# Switch.net
KiCad netlist of a schematic drawn in Altium Designer
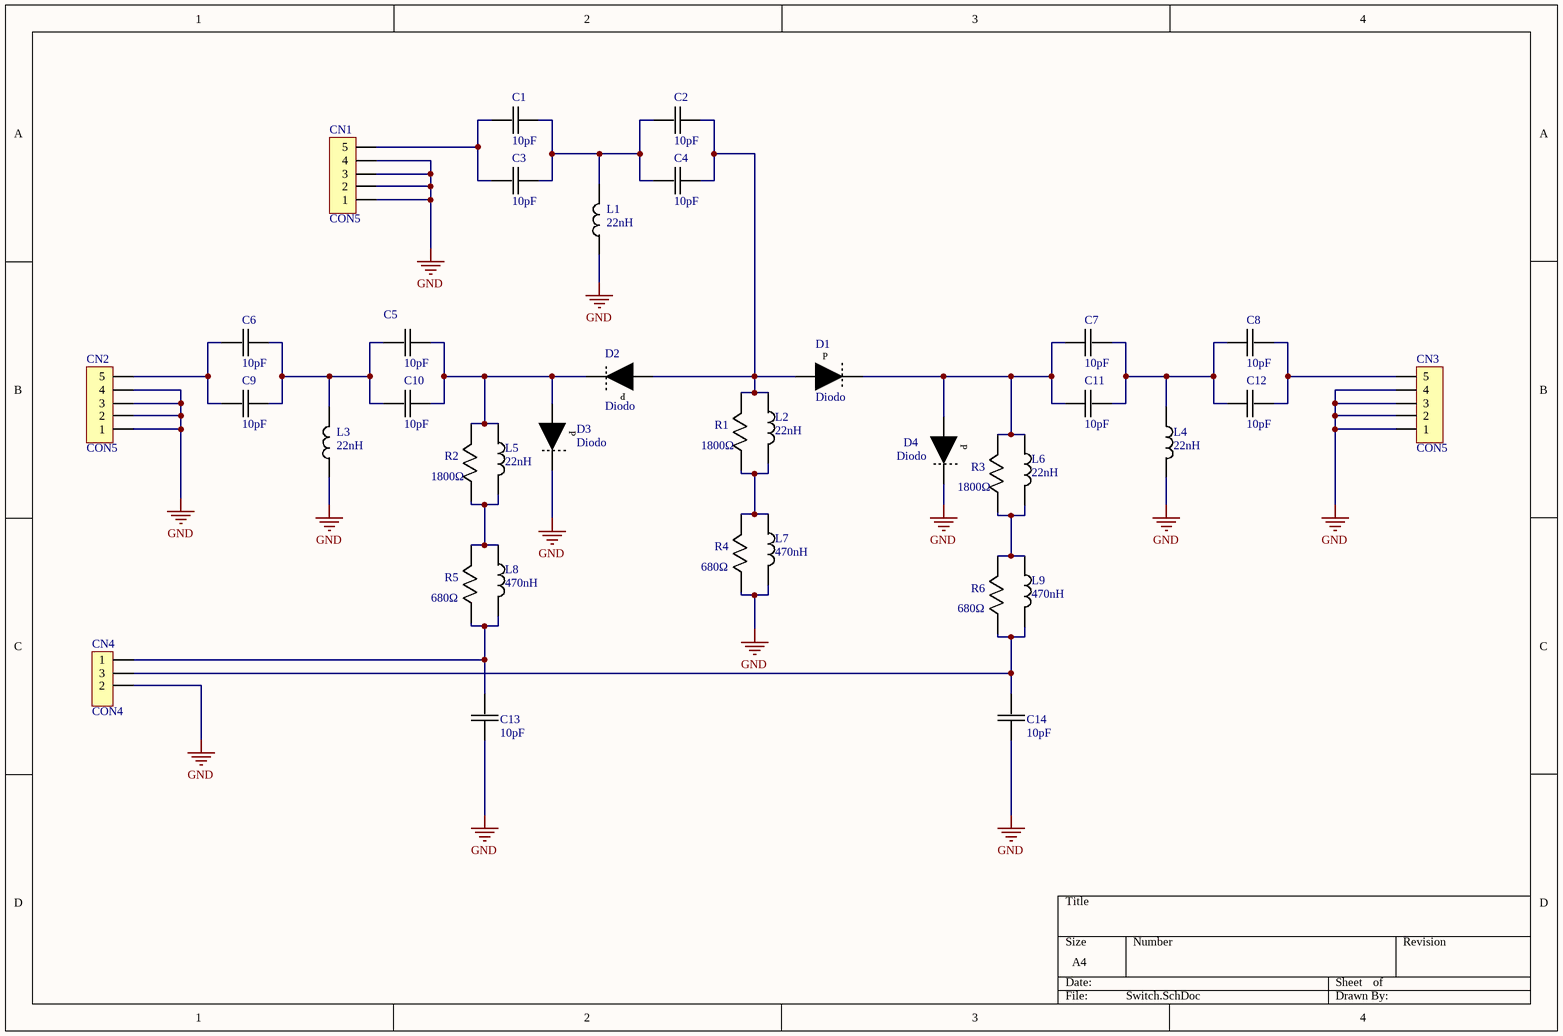
[diagram p0: Switch.SchDoc]

(export (version "E")
  (design (tool "Eeschema 10.0.6"))
  (components
    (comp (ref "C1")
      (value "10pF")
      (footprint "C_0603")
      (description "Capacitor")
      (libsource (lib "Switch") (part "C_0603"))
    )
    (comp (ref "C2")
      (value "10pF")
      (footprint "C_0603")
      (description "Capacitor")
      (libsource (lib "Switch") (part "C_0603"))
    )
    (comp (ref "C3")
      (value "10pF")
      (footprint "C_0603")
      (description "Capacitor")
      (libsource (lib "Switch") (part "C_0603"))
    )
    (comp (ref "C4")
      (value "10pF")
      (footprint "C_0603")
      (description "Capacitor")
      (libsource (lib "Switch") (part "C_0603"))
    )
    (comp (ref "C5")
      (value "10pF")
      (footprint "C_0603")
      (description "Capacitor")
      (libsource (lib "Switch") (part "C_0603"))
    )
    (comp (ref "C6")
      (value "10pF")
      (footprint "C_0603")
      (description "Capacitor")
      (libsource (lib "Switch") (part "C_0603"))
    )
    (comp (ref "C7")
      (value "10pF")
      (footprint "C_0603")
      (description "Capacitor")
      (libsource (lib "Switch") (part "C_0603"))
    )
    (comp (ref "C8")
      (value "10pF")
      (footprint "C_0603")
      (description "Capacitor")
      (libsource (lib "Switch") (part "C_0603"))
    )
    (comp (ref "C9")
      (value "10pF")
      (footprint "C_0603")
      (description "Capacitor")
      (libsource (lib "Switch") (part "C_0603"))
    )
    (comp (ref "C10")
      (value "10pF")
      (footprint "C_0603")
      (description "Capacitor")
      (libsource (lib "Switch") (part "C_0603"))
    )
    (comp (ref "C11")
      (value "10pF")
      (footprint "C_0603")
      (description "Capacitor")
      (libsource (lib "Switch") (part "C_0603"))
    )
    (comp (ref "C12")
      (value "10pF")
      (footprint "C_0603")
      (description "Capacitor")
      (libsource (lib "Switch") (part "C_0603"))
    )
    (comp (ref "C13")
      (value "10pF")
      (footprint "C_0603")
      (description "Capacitor")
      (libsource (lib "Switch") (part "C_0603"))
    )
    (comp (ref "C14")
      (value "10pF")
      (footprint "C_0603")
      (description "Capacitor")
      (libsource (lib "Switch") (part "C_0603"))
    )
    (comp (ref "CN1")
      (value "CON5")
      (footprint "SMA")
      (description "Conector SMA")
      (libsource (lib "Switch") (part "CON5"))
    )
    (comp (ref "CN2")
      (value "CON5")
      (footprint "SMA")
      (description "Conector SMA")
      (libsource (lib "Switch") (part "CON5"))
    )
    (comp (ref "CN3")
      (value "CON5")
      (footprint "SMA")
      (description "Conector SMA")
      (libsource (lib "") (part "CON5_1"))
    )
    (comp (ref "CN4")
      (value "CON4")
      (footprint "CON3")
      (description "Conector SMA")
      (libsource (lib "Switch") (part "CON4"))
    )
    (comp (ref "D1")
      (value "Diodo")
      (footprint "SC79")
      (description "Diodo Pin")
      (libsource (lib "Switch") (part "Diodo"))
    )
    (comp (ref "D2")
      (value "Diodo")
      (footprint "SC79")
      (description "Diodo Pin")
      (libsource (lib "Switch") (part "Diodo"))
    )
    (comp (ref "D3")
      (value "Diodo")
      (footprint "SC79")
      (description "Diodo Pin")
      (libsource (lib "Switch") (part "Diodo"))
    )
    (comp (ref "D4")
      (value "Diodo")
      (footprint "SC79")
      (description "Diodo Pin")
      (libsource (lib "Switch") (part "Diodo"))
    )
    (comp (ref "L1")
      (value "22nH")
      (footprint "L_0603")
      (description "Inductor")
      (libsource (lib "Switch") (part "L_0603"))
    )
    (comp (ref "L2")
      (value "22nH")
      (footprint "L_0603")
      (description "Inductor")
      (libsource (lib "Switch") (part "L_0603"))
    )
    (comp (ref "L3")
      (value "22nH")
      (footprint "L_0603")
      (description "Inductor")
      (libsource (lib "Switch") (part "L_0603"))
    )
    (comp (ref "L4")
      (value "22nH")
      (footprint "L_0603")
      (description "Inductor")
      (libsource (lib "") (part "L_0603_1"))
    )
    (comp (ref "L5")
      (value "22nH")
      (footprint "L_0603")
      (description "Inductor")
      (libsource (lib "Switch") (part "L_0603"))
    )
    (comp (ref "L6")
      (value "22nH")
      (footprint "L_0603")
      (description "Inductor")
      (libsource (lib "Switch") (part "L_0603"))
    )
    (comp (ref "L7")
      (value "470nH")
      (footprint "L_0603")
      (description "Inductor")
      (libsource (lib "Switch") (part "L_0603"))
    )
    (comp (ref "L8")
      (value "470nH")
      (footprint "L_0603")
      (description "Inductor")
      (libsource (lib "Switch") (part "L_0603"))
    )
    (comp (ref "L9")
      (value "470nH")
      (footprint "L_0603")
      (description "Inductor")
      (libsource (lib "Switch") (part "L_0603"))
    )
    (comp (ref "R1")
      (value "1800Ω")
      (footprint "R_0603")
      (description "Resistor")
      (libsource (lib "Switch") (part "R_0805"))
    )
    (comp (ref "R2")
      (value "1800Ω")
      (footprint "R_0603")
      (description "Resistor")
      (libsource (lib "Switch") (part "R_0805"))
    )
    (comp (ref "R3")
      (value "1800Ω")
      (footprint "R_0603")
      (description "Resistor")
      (libsource (lib "Switch") (part "R_0805"))
    )
    (comp (ref "R4")
      (value "680Ω")
      (footprint "R_0603")
      (description "Resistor")
      (libsource (lib "Switch") (part "R_0805"))
    )
    (comp (ref "R5")
      (value "680Ω")
      (footprint "R_0603")
      (description "Resistor")
      (libsource (lib "Switch") (part "R_0805"))
    )
    (comp (ref "R6")
      (value "680Ω")
      (footprint "R_0603")
      (description "Resistor")
      (libsource (lib "Switch") (part "R_0805"))
    )
  )
  (nets
    (net (code "1") (name "GND") (class "Default")
      (node (ref "C13") (pin "2") (pinfunction "2_2") (pintype "passive"))
      (node (ref "C14") (pin "2") (pinfunction "2_2") (pintype "passive"))
      (node (ref "CN1") (pin "1") (pinfunction "1_1") (pintype "passive"))
      (node (ref "CN1") (pin "2") (pinfunction "2_2") (pintype "passive"))
      (node (ref "CN1") (pin "3") (pinfunction "3_3") (pintype "passive"))
      (node (ref "CN1") (pin "4") (pinfunction "4_4") (pintype "passive"))
      (node (ref "CN2") (pin "1") (pinfunction "1_1") (pintype "passive"))
      (node (ref "CN2") (pin "2") (pinfunction "2_2") (pintype "passive"))
      (node (ref "CN2") (pin "3") (pinfunction "3_3") (pintype "passive"))
      (node (ref "CN2") (pin "4") (pinfunction "4_4") (pintype "passive"))
      (node (ref "CN3") (pin "1") (pinfunction "1_1") (pintype "passive"))
      (node (ref "CN3") (pin "2") (pinfunction "2_2") (pintype "passive"))
      (node (ref "CN3") (pin "3") (pinfunction "3_3") (pintype "passive"))
      (node (ref "CN3") (pin "4") (pinfunction "4_4") (pintype "passive"))
      (node (ref "CN4") (pin "2") (pinfunction "2_2") (pintype "passive"))
      (node (ref "D3") (pin "K") (pinfunction "K_K") (pintype "passive"))
      (node (ref "D4") (pin "K") (pinfunction "K_K") (pintype "passive"))
      (node (ref "L1") (pin "2") (pinfunction "2_2") (pintype "passive"))
      (node (ref "L3") (pin "2") (pinfunction "2_2") (pintype "passive"))
      (node (ref "L4") (pin "2") (pinfunction "2_2") (pintype "passive"))
      (node (ref "L7") (pin "1") (pinfunction "1_1") (pintype "passive"))
      (node (ref "R4") (pin "1") (pinfunction "1_1") (pintype "passive"))
    )
    (net (code "2") (name "Net-(C1-Pad1)") (class "Default")
      (node (ref "C1") (pin "1") (pinfunction "1_1") (pintype "passive"))
      (node (ref "C3") (pin "1") (pinfunction "1_1") (pintype "passive"))
      (node (ref "CN1") (pin "5") (pinfunction "5_5") (pintype "passive"))
    )
    (net (code "3") (name "Net-(C1-Pad2)") (class "Default")
      (node (ref "C1") (pin "2") (pinfunction "2_2") (pintype "passive"))
      (node (ref "C2") (pin "1") (pinfunction "1_1") (pintype "passive"))
      (node (ref "C3") (pin "2") (pinfunction "2_2") (pintype "passive"))
      (node (ref "C4") (pin "1") (pinfunction "1_1") (pintype "passive"))
      (node (ref "L1") (pin "1") (pinfunction "1_1") (pintype "passive"))
    )
    (net (code "4") (name "Net-(C2-Pad2)") (class "Default")
      (node (ref "C2") (pin "2") (pinfunction "2_2") (pintype "passive"))
      (node (ref "C4") (pin "2") (pinfunction "2_2") (pintype "passive"))
      (node (ref "D1") (pin "A") (pinfunction "A_A") (pintype "passive"))
      (node (ref "D2") (pin "A") (pinfunction "A_A") (pintype "passive"))
      (node (ref "L2") (pin "2") (pinfunction "2_2") (pintype "passive"))
      (node (ref "R1") (pin "2") (pinfunction "2_2") (pintype "passive"))
    )
    (net (code "5") (name "Net-(C6-Pad1)") (class "Default")
      (node (ref "C6") (pin "1") (pinfunction "1_1") (pintype "passive"))
      (node (ref "C9") (pin "1") (pinfunction "1_1") (pintype "passive"))
      (node (ref "CN2") (pin "5") (pinfunction "5_5") (pintype "passive"))
    )
    (net (code "6") (name "Net-(C10-Pad1)") (class "Default")
      (node (ref "C10") (pin "1") (pinfunction "1_1") (pintype "passive"))
      (node (ref "C5") (pin "1") (pinfunction "1_1") (pintype "passive"))
      (node (ref "C6") (pin "2") (pinfunction "2_2") (pintype "passive"))
      (node (ref "C9") (pin "2") (pinfunction "2_2") (pintype "passive"))
      (node (ref "L3") (pin "1") (pinfunction "1_1") (pintype "passive"))
    )
    (net (code "7") (name "Net-(C10-Pad2)") (class "Default")
      (node (ref "C10") (pin "2") (pinfunction "2_2") (pintype "passive"))
      (node (ref "C5") (pin "2") (pinfunction "2_2") (pintype "passive"))
      (node (ref "D2") (pin "K") (pinfunction "K_K") (pintype "passive"))
      (node (ref "D3") (pin "A") (pinfunction "A_A") (pintype "passive"))
      (node (ref "L5") (pin "2") (pinfunction "2_2") (pintype "passive"))
      (node (ref "R2") (pin "2") (pinfunction "2_2") (pintype "passive"))
    )
    (net (code "8") (name "Net-(C11-Pad1)") (class "Default")
      (node (ref "C11") (pin "1") (pinfunction "1_1") (pintype "passive"))
      (node (ref "C12") (pin "2") (pinfunction "2_2") (pintype "passive"))
      (node (ref "C7") (pin "1") (pinfunction "1_1") (pintype "passive"))
      (node (ref "C8") (pin "2") (pinfunction "2_2") (pintype "passive"))
      (node (ref "L4") (pin "1") (pinfunction "1_1") (pintype "passive"))
    )
    (net (code "9") (name "Net-(C11-Pad2)") (class "Default")
      (node (ref "C11") (pin "2") (pinfunction "2_2") (pintype "passive"))
      (node (ref "C7") (pin "2") (pinfunction "2_2") (pintype "passive"))
      (node (ref "D1") (pin "K") (pinfunction "K_K") (pintype "passive"))
      (node (ref "D4") (pin "A") (pinfunction "A_A") (pintype "passive"))
      (node (ref "L6") (pin "2") (pinfunction "2_2") (pintype "passive"))
      (node (ref "R3") (pin "2") (pinfunction "2_2") (pintype "passive"))
    )
    (net (code "10") (name "Net-(C12-Pad1)") (class "Default")
      (node (ref "C12") (pin "1") (pinfunction "1_1") (pintype "passive"))
      (node (ref "C8") (pin "1") (pinfunction "1_1") (pintype "passive"))
      (node (ref "CN3") (pin "5") (pinfunction "5_5") (pintype "passive"))
    )
    (net (code "11") (name "Net-(C13-Pad1)") (class "Default")
      (node (ref "C13") (pin "1") (pinfunction "1_1") (pintype "passive"))
      (node (ref "CN4") (pin "1") (pinfunction "1_1") (pintype "passive"))
      (node (ref "L8") (pin "1") (pinfunction "1_1") (pintype "passive"))
      (node (ref "R5") (pin "1") (pinfunction "1_1") (pintype "passive"))
    )
    (net (code "12") (name "Net-(C14-Pad1)") (class "Default")
      (node (ref "C14") (pin "1") (pinfunction "1_1") (pintype "passive"))
      (node (ref "CN4") (pin "3") (pinfunction "3_3") (pintype "passive"))
      (node (ref "L9") (pin "1") (pinfunction "1_1") (pintype "passive"))
      (node (ref "R6") (pin "1") (pinfunction "1_1") (pintype "passive"))
    )
    (net (code "13") (name "Net-(L2-Pad1)") (class "Default")
      (node (ref "L2") (pin "1") (pinfunction "1_1") (pintype "passive"))
      (node (ref "L7") (pin "2") (pinfunction "2_2") (pintype "passive"))
      (node (ref "R1") (pin "1") (pinfunction "1_1") (pintype "passive"))
      (node (ref "R4") (pin "2") (pinfunction "2_2") (pintype "passive"))
    )
    (net (code "14") (name "Net-(L5-Pad1)") (class "Default")
      (node (ref "L5") (pin "1") (pinfunction "1_1") (pintype "passive"))
      (node (ref "L8") (pin "2") (pinfunction "2_2") (pintype "passive"))
      (node (ref "R2") (pin "1") (pinfunction "1_1") (pintype "passive"))
      (node (ref "R5") (pin "2") (pinfunction "2_2") (pintype "passive"))
    )
    (net (code "15") (name "Net-(L6-Pad1)") (class "Default")
      (node (ref "L6") (pin "1") (pinfunction "1_1") (pintype "passive"))
      (node (ref "L9") (pin "2") (pinfunction "2_2") (pintype "passive"))
      (node (ref "R3") (pin "1") (pinfunction "1_1") (pintype "passive"))
      (node (ref "R6") (pin "2") (pinfunction "2_2") (pintype "passive"))
    )
  )
)
